# GCDuino3v3.net
KiCad netlist of a schematic drawn in EAGLE
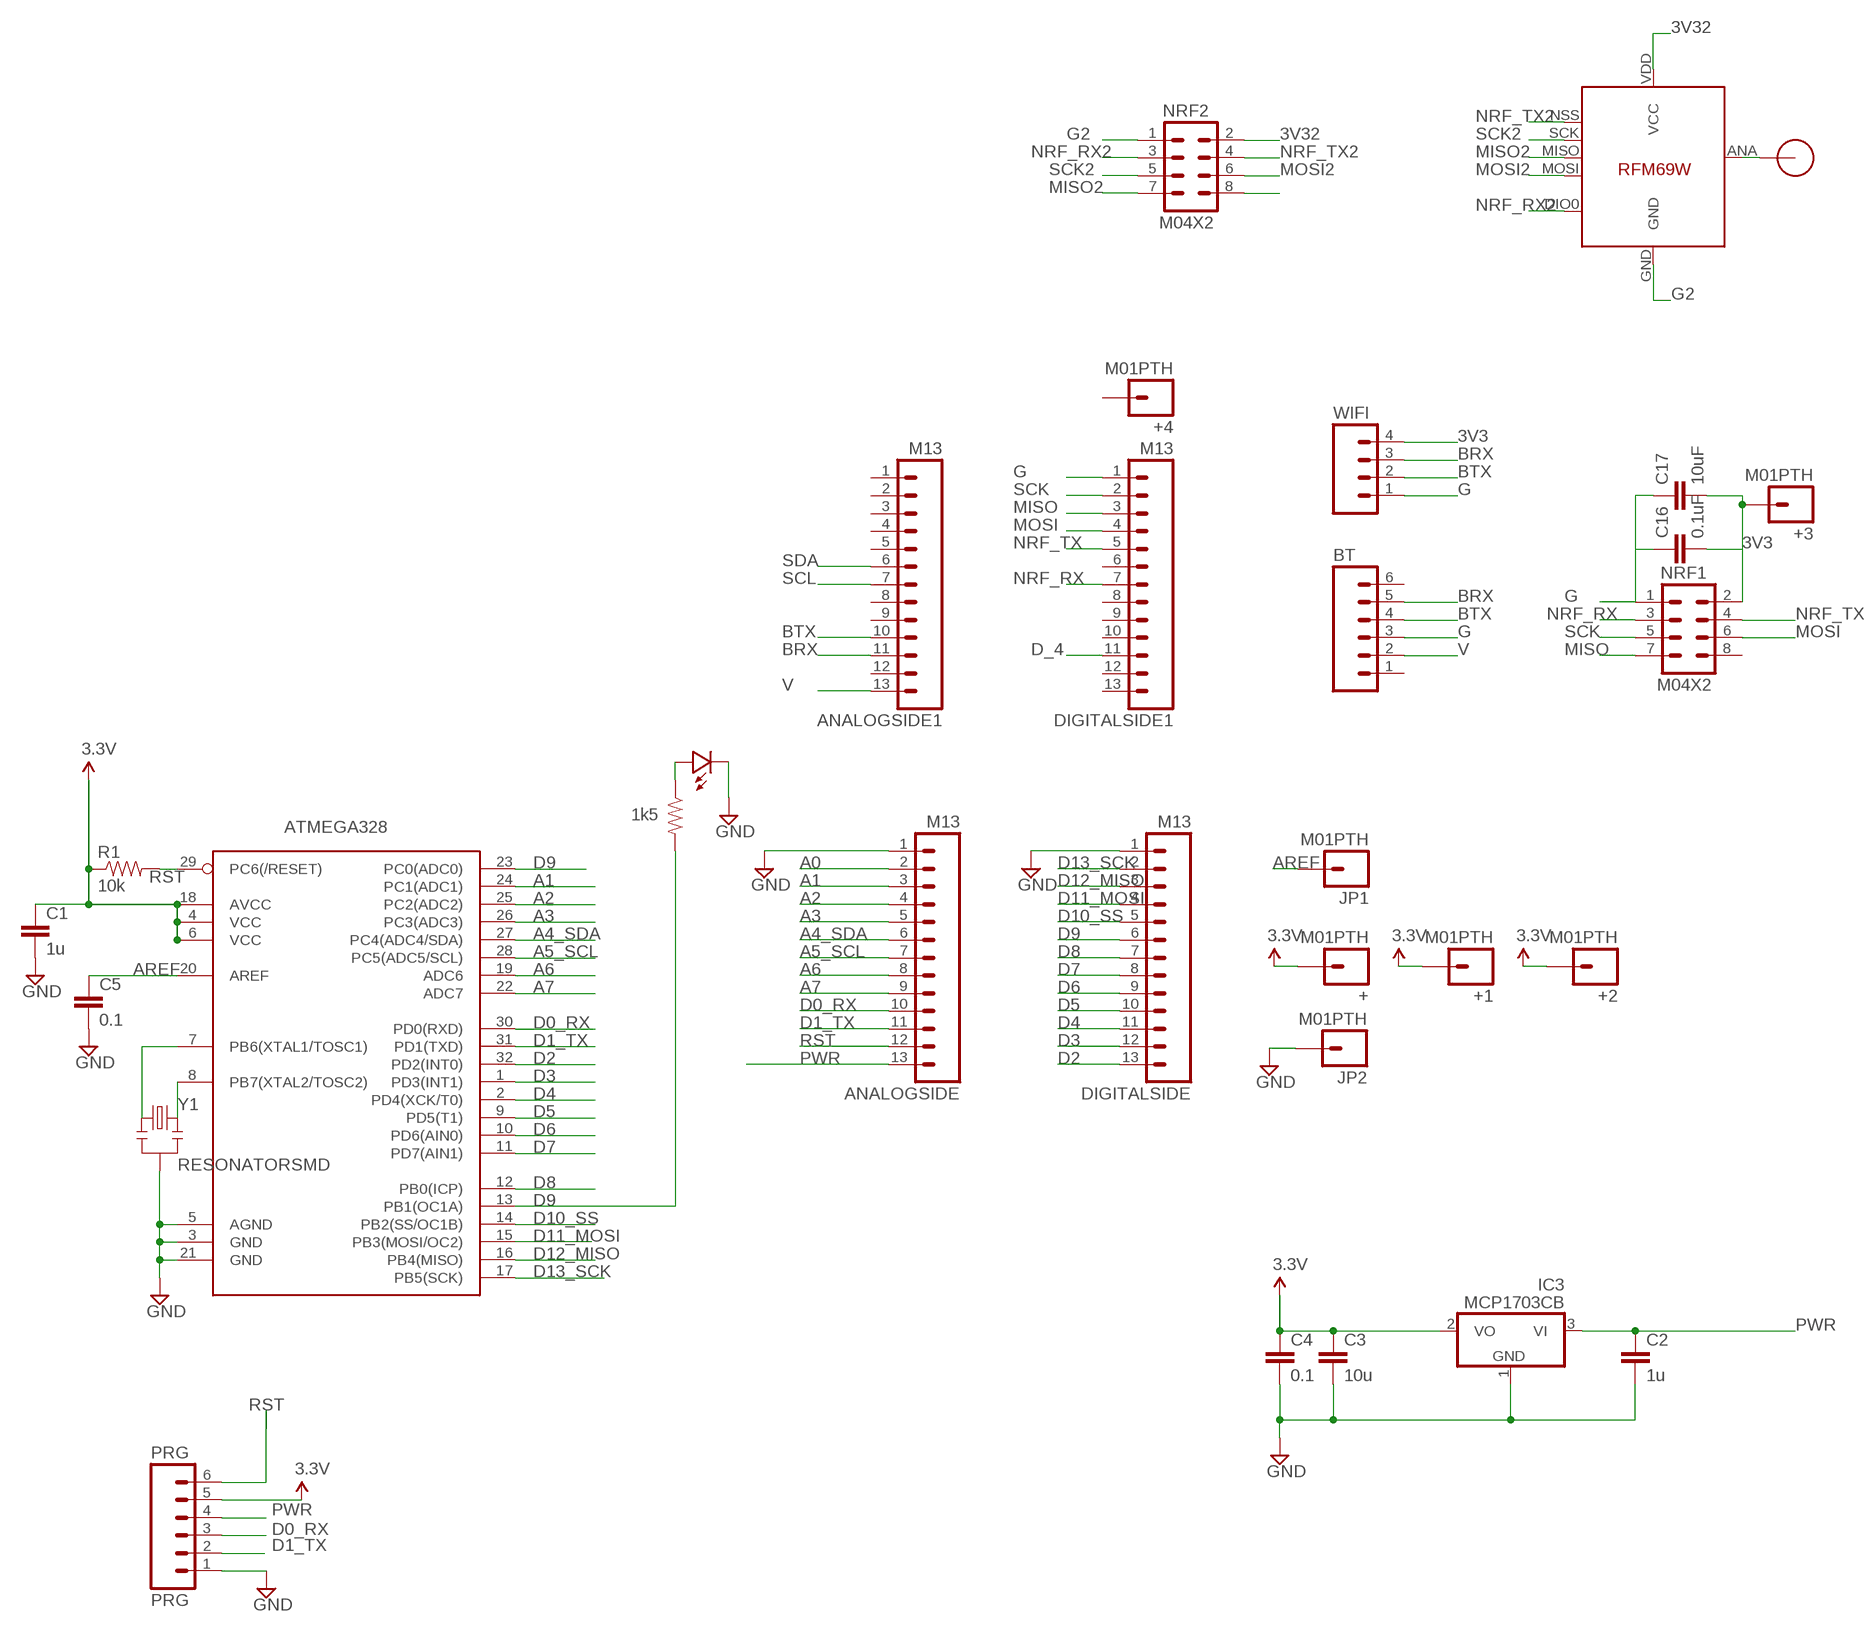
[diagram p0: schematic, sheet 1]

(export (version "E")
  (design (tool "Eeschema 10.0.6"))
  (components
    (comp (ref "+")
      (value "M01PTH")
      (footprint "eagle-import:1X01")
      (libsource (lib "eagle-import") (part "M01PTH"))
    )
    (comp (ref "+1")
      (value "M01PTH")
      (footprint "eagle-import:1X01")
      (libsource (lib "eagle-import") (part "M01PTH"))
    )
    (comp (ref "+2")
      (value "M01PTH")
      (footprint "eagle-import:1X01")
      (libsource (lib "eagle-import") (part "M01PTH"))
    )
    (comp (ref "+3")
      (value "M01PTH")
      (footprint "eagle-import:1X01")
      (libsource (lib "eagle-import") (part "M01PTH"))
    )
    (comp (ref "+4")
      (value "M01PTH")
      (footprint "eagle-import:1X01")
      (libsource (lib "eagle-import") (part "M01PTH"))
    )
    (comp (ref "ANALOGSIDE")
      (value "M13")
      (footprint "eagle-import:1X13")
      (libsource (lib "eagle-import") (part "M13"))
    )
    (comp (ref "ANALOGSIDE1")
      (value "M13")
      (footprint "eagle-import:1X13")
      (libsource (lib "eagle-import") (part "M13"))
    )
    (comp (ref "ATMEGA328")
      (value "ATMega-328")
      (footprint "eagle-import:TQFP32-08")
      (libsource (lib "eagle-import") (part "ATMEGA168/328TQFP32"))
    )
    (comp (ref "BT")
      (value "M06SIP")
      (footprint "eagle-import:1X06")
      (libsource (lib "eagle-import") (part "M06SIP"))
    )
    (comp (ref "C1")
      (value "1u")
      (footprint "eagle-import:0805")
      (libsource (lib "eagle-import") (part "CAP0805"))
    )
    (comp (ref "C2")
      (value "1u")
      (footprint "eagle-import:0805")
      (libsource (lib "eagle-import") (part "CAP0805"))
    )
    (comp (ref "C3")
      (value "10u")
      (footprint "eagle-import:0805-CAP")
      (libsource (lib "eagle-import") (part "CAP0805-CAP"))
    )
    (comp (ref "C4")
      (value "0.1")
      (footprint "eagle-import:0805")
      (libsource (lib "eagle-import") (part "CAP0805"))
    )
    (comp (ref "C5")
      (value "0.1")
      (footprint "eagle-import:0805")
      (libsource (lib "eagle-import") (part "CAP0805"))
    )
    (comp (ref "C16")
      (value "0.1uF")
      (footprint "eagle-import:0805")
      (libsource (lib "eagle-import") (part "SparkFun-Capacitors_CAP0805"))
    )
    (comp (ref "C17")
      (value "10uF")
      (footprint "eagle-import:0805")
      (libsource (lib "eagle-import") (part "SparkFun-Capacitors_CAP0805"))
    )
    (comp (ref "DIGITALSIDE")
      (value "M13")
      (footprint "eagle-import:1X13")
      (libsource (lib "eagle-import") (part "M13"))
    )
    (comp (ref "DIGITALSIDE1")
      (value "M13")
      (footprint "eagle-import:1X13")
      (libsource (lib "eagle-import") (part "M13"))
    )
    (comp (ref "IC3")
      (value "MCP1703CB")
      (footprint "eagle-import:SOT23")
      (libsource (lib "eagle-import") (part "MCP1703CB"))
    )
    (comp (ref "JP1")
      (value "M01PTH")
      (footprint "eagle-import:1X01")
      (libsource (lib "eagle-import") (part "M01PTH"))
    )
    (comp (ref "JP2")
      (value "M01PTH")
      (footprint "eagle-import:1X01")
      (libsource (lib "eagle-import") (part "M01PTH"))
    )
    (comp (ref "NRF1")
      (value "M04X2")
      (footprint "eagle-import:2X4")
      (libsource (lib "eagle-import") (part "M04X2"))
    )
    (comp (ref "NRF2")
      (value "M04X2")
      (footprint "eagle-import:2X4")
      (libsource (lib "eagle-import") (part "M04X2"))
    )
    (comp (ref "PRG")
      (value "PRG")
      (footprint "eagle-import:1X06")
      (libsource (lib "eagle-import") (part "M06SIP"))
    )
    (comp (ref "R1")
      (value "10k")
      (footprint "eagle-import:0805")
      (libsource (lib "eagle-import") (part "RESISTOR0805"))
    )
    (comp (ref "R2")
      (value "1k5")
      (footprint "eagle-import:0805")
      (libsource (lib "eagle-import") (part "RESISTOR0805"))
    )
    (comp (ref "U$2")
      (value "LED0805")
      (footprint "eagle-import:0805-LED")
      (libsource (lib "eagle-import") (part "LED0805"))
    )
    (comp (ref "U$5")
      (value "RFM69")
      (footprint "eagle-import:RFM69W-MINPADS")
      (libsource (lib "eagle-import") (part "RFM69"))
    )
    (comp (ref "U$8")
      (value "RFM12B_ANTENNA")
      (footprint "eagle-import:RFM12B-ANTENNA")
      (libsource (lib "eagle-import") (part "RFM12B_ANTENNA"))
    )
    (comp (ref "WIFI")
      (value "M04PTH")
      (footprint "eagle-import:1X04")
      (libsource (lib "eagle-import") (part "M04PTH"))
    )
    (comp (ref "Y1")
      (value "RESONATORSMD")
      (footprint "eagle-import:RESONATOR-SMD")
      (libsource (lib "eagle-import") (part "RESONATORSMD"))
    )
  )
  (nets
    (net (code "1") (name "/3V3") (class "Default")
      (node (ref "+3") (pin "1") (pinfunction "1_1") (pintype "passive"))
      (node (ref "C16") (pin "2") (pinfunction "2_2") (pintype "passive"))
      (node (ref "C17") (pin "2") (pinfunction "2_2") (pintype "passive"))
      (node (ref "NRF1") (pin "2") (pinfunction "2_2") (pintype "passive"))
      (node (ref "WIFI") (pin "4") (pinfunction "4_4") (pintype "passive"))
    )
    (net (code "2") (name "/3V32") (class "Default")
      (node (ref "NRF2") (pin "2") (pinfunction "2_2") (pintype "passive"))
      (node (ref "U$5") (pin "VDD") (pinfunction "VCC_VDD") (pintype "power_in"))
    )
    (net (code "3") (name "/A0") (class "Default")
      (node (ref "ANALOGSIDE") (pin "2") (pinfunction "2_2") (pintype "passive"))
      (node (ref "ATMEGA328") (pin "23") (pinfunction "PC0(ADC0)_23") (pintype "bidirectional"))
    )
    (net (code "4") (name "/A1") (class "Default")
      (node (ref "ANALOGSIDE") (pin "3") (pinfunction "3_3") (pintype "passive"))
      (node (ref "ATMEGA328") (pin "24") (pinfunction "PC1(ADC1)_24") (pintype "bidirectional"))
    )
    (net (code "5") (name "/A2") (class "Default")
      (node (ref "ANALOGSIDE") (pin "4") (pinfunction "4_4") (pintype "passive"))
      (node (ref "ATMEGA328") (pin "25") (pinfunction "PC2(ADC2)_25") (pintype "bidirectional"))
    )
    (net (code "6") (name "/A3") (class "Default")
      (node (ref "ANALOGSIDE") (pin "5") (pinfunction "5_5") (pintype "passive"))
      (node (ref "ATMEGA328") (pin "26") (pinfunction "PC3(ADC3)_26") (pintype "bidirectional"))
    )
    (net (code "7") (name "/A4_SDA") (class "Default")
      (node (ref "ANALOGSIDE") (pin "6") (pinfunction "6_6") (pintype "passive"))
      (node (ref "ATMEGA328") (pin "27") (pinfunction "PC4(ADC4/SDA)_27") (pintype "bidirectional"))
    )
    (net (code "8") (name "/A5_SCL") (class "Default")
      (node (ref "ANALOGSIDE") (pin "7") (pinfunction "7_7") (pintype "passive"))
      (node (ref "ATMEGA328") (pin "28") (pinfunction "PC5(ADC5/SCL)_28") (pintype "bidirectional"))
    )
    (net (code "9") (name "/A6") (class "Default")
      (node (ref "ANALOGSIDE") (pin "8") (pinfunction "8_8") (pintype "passive"))
      (node (ref "ATMEGA328") (pin "19") (pinfunction "ADC6_19") (pintype "bidirectional"))
    )
    (net (code "10") (name "/A7") (class "Default")
      (node (ref "ANALOGSIDE") (pin "9") (pinfunction "9_9") (pintype "passive"))
      (node (ref "ATMEGA328") (pin "22") (pinfunction "ADC7_22") (pintype "bidirectional"))
    )
    (net (code "11") (name "/AREF") (class "Default")
      (node (ref "ATMEGA328") (pin "20") (pinfunction "AREF_20") (pintype "bidirectional"))
      (node (ref "C5") (pin "1") (pinfunction "1_1") (pintype "passive"))
      (node (ref "JP1") (pin "1") (pinfunction "1_1") (pintype "passive"))
    )
    (net (code "12") (name "/BRX") (class "Default")
      (node (ref "ANALOGSIDE1") (pin "11") (pinfunction "11_11") (pintype "passive"))
      (node (ref "BT") (pin "5") (pinfunction "5_5") (pintype "passive"))
      (node (ref "WIFI") (pin "3") (pinfunction "3_3") (pintype "passive"))
    )
    (net (code "13") (name "/BTX") (class "Default")
      (node (ref "ANALOGSIDE1") (pin "10") (pinfunction "10_10") (pintype "passive"))
      (node (ref "BT") (pin "4") (pinfunction "4_4") (pintype "passive"))
      (node (ref "WIFI") (pin "2") (pinfunction "2_2") (pintype "passive"))
    )
    (net (code "14") (name "/D0_RX") (class "Default")
      (node (ref "ANALOGSIDE") (pin "10") (pinfunction "10_10") (pintype "passive"))
      (node (ref "ATMEGA328") (pin "30") (pinfunction "PD0(RXD)_30") (pintype "bidirectional"))
      (node (ref "PRG") (pin "3") (pinfunction "3_3") (pintype "passive"))
    )
    (net (code "15") (name "/D1_TX") (class "Default")
      (node (ref "ANALOGSIDE") (pin "11") (pinfunction "11_11") (pintype "passive"))
      (node (ref "ATMEGA328") (pin "31") (pinfunction "PD1(TXD)_31") (pintype "bidirectional"))
      (node (ref "PRG") (pin "2") (pinfunction "2_2") (pintype "passive"))
    )
    (net (code "16") (name "/D2") (class "Default")
      (node (ref "ATMEGA328") (pin "32") (pinfunction "PD2(INT0)_32") (pintype "bidirectional"))
      (node (ref "DIGITALSIDE") (pin "13") (pinfunction "13_13") (pintype "passive"))
    )
    (net (code "17") (name "/D3") (class "Default")
      (node (ref "ATMEGA328") (pin "1") (pinfunction "PD3(INT1)_1") (pintype "bidirectional"))
      (node (ref "DIGITALSIDE") (pin "12") (pinfunction "12_12") (pintype "passive"))
    )
    (net (code "18") (name "/D4") (class "Default")
      (node (ref "ATMEGA328") (pin "2") (pinfunction "PD4(XCK/T0)_2") (pintype "bidirectional"))
      (node (ref "DIGITALSIDE") (pin "11") (pinfunction "11_11") (pintype "passive"))
    )
    (net (code "19") (name "/D5") (class "Default")
      (node (ref "ATMEGA328") (pin "9") (pinfunction "PD5(T1)_9") (pintype "bidirectional"))
      (node (ref "DIGITALSIDE") (pin "10") (pinfunction "10_10") (pintype "passive"))
    )
    (net (code "20") (name "/D6") (class "Default")
      (node (ref "ATMEGA328") (pin "10") (pinfunction "PD6(AIN0)_10") (pintype "bidirectional"))
      (node (ref "DIGITALSIDE") (pin "9") (pinfunction "9_9") (pintype "passive"))
    )
    (net (code "21") (name "/D7") (class "Default")
      (node (ref "ATMEGA328") (pin "11") (pinfunction "PD7(AIN1)_11") (pintype "bidirectional"))
      (node (ref "DIGITALSIDE") (pin "8") (pinfunction "8_8") (pintype "passive"))
    )
    (net (code "22") (name "/D8") (class "Default")
      (node (ref "ATMEGA328") (pin "12") (pinfunction "PB0(ICP)_12") (pintype "bidirectional"))
      (node (ref "DIGITALSIDE") (pin "7") (pinfunction "7_7") (pintype "passive"))
    )
    (net (code "23") (name "/D9") (class "Default")
      (node (ref "ATMEGA328") (pin "13") (pinfunction "PB1(OC1A)_13") (pintype "bidirectional"))
      (node (ref "DIGITALSIDE") (pin "6") (pinfunction "6_6") (pintype "passive"))
      (node (ref "R2") (pin "2") (pinfunction "2_2") (pintype "passive"))
    )
    (net (code "24") (name "/D10_SS") (class "Default")
      (node (ref "ATMEGA328") (pin "14") (pinfunction "PB2(SS/OC1B)_14") (pintype "bidirectional"))
      (node (ref "DIGITALSIDE") (pin "5") (pinfunction "5_5") (pintype "passive"))
    )
    (net (code "25") (name "/D11_MOSI") (class "Default")
      (node (ref "ATMEGA328") (pin "15") (pinfunction "PB3(MOSI/OC2)_15") (pintype "bidirectional"))
      (node (ref "DIGITALSIDE") (pin "4") (pinfunction "4_4") (pintype "passive"))
    )
    (net (code "26") (name "/D12_MISO") (class "Default")
      (node (ref "ATMEGA328") (pin "16") (pinfunction "PB4(MISO)_16") (pintype "bidirectional"))
      (node (ref "DIGITALSIDE") (pin "3") (pinfunction "3_3") (pintype "passive"))
    )
    (net (code "27") (name "/D13_SCK") (class "Default")
      (node (ref "ATMEGA328") (pin "17") (pinfunction "PB5(SCK)_17") (pintype "bidirectional"))
      (node (ref "DIGITALSIDE") (pin "2") (pinfunction "2_2") (pintype "passive"))
    )
    (net (code "28") (name "/D_4") (class "Default")
      (node (ref "DIGITALSIDE1") (pin "11") (pinfunction "11_11") (pintype "passive"))
    )
    (net (code "29") (name "/G") (class "Default")
      (node (ref "BT") (pin "3") (pinfunction "3_3") (pintype "passive"))
      (node (ref "C16") (pin "1") (pinfunction "1_1") (pintype "passive"))
      (node (ref "C17") (pin "1") (pinfunction "1_1") (pintype "passive"))
      (node (ref "DIGITALSIDE1") (pin "1") (pinfunction "1_1") (pintype "passive"))
      (node (ref "NRF1") (pin "1") (pinfunction "1_1") (pintype "passive"))
      (node (ref "WIFI") (pin "1") (pinfunction "1_1") (pintype "passive"))
    )
    (net (code "30") (name "/G2") (class "Default")
      (node (ref "NRF2") (pin "1") (pinfunction "1_1") (pintype "passive"))
      (node (ref "U$5") (pin "GND") (pinfunction "GND_GND") (pintype "power_in"))
    )
    (net (code "31") (name "/MISO") (class "Default")
      (node (ref "DIGITALSIDE1") (pin "3") (pinfunction "3_3") (pintype "passive"))
      (node (ref "NRF1") (pin "7") (pinfunction "7_7") (pintype "passive"))
    )
    (net (code "32") (name "/MISO2") (class "Default")
      (node (ref "NRF2") (pin "7") (pinfunction "7_7") (pintype "passive"))
      (node (ref "U$5") (pin "MISO") (pinfunction "MISO_MISO") (pintype "input"))
    )
    (net (code "33") (name "/MOSI") (class "Default")
      (node (ref "DIGITALSIDE1") (pin "4") (pinfunction "4_4") (pintype "passive"))
      (node (ref "NRF1") (pin "6") (pinfunction "6_6") (pintype "passive"))
    )
    (net (code "34") (name "/MOSI2") (class "Default")
      (node (ref "NRF2") (pin "6") (pinfunction "6_6") (pintype "passive"))
      (node (ref "U$5") (pin "MOSI") (pinfunction "MOSI_MOSI") (pintype "output"))
    )
    (net (code "35") (name "/NRF_RX") (class "Default")
      (node (ref "DIGITALSIDE1") (pin "7") (pinfunction "7_7") (pintype "passive"))
      (node (ref "NRF1") (pin "3") (pinfunction "3_3") (pintype "passive"))
    )
    (net (code "36") (name "/NRF_RX2") (class "Default")
      (node (ref "NRF2") (pin "3") (pinfunction "3_3") (pintype "passive"))
      (node (ref "U$5") (pin "DIO0") (pinfunction "DIO0_DIO0") (pintype "open_collector"))
    )
    (net (code "37") (name "/NRF_TX") (class "Default")
      (node (ref "DIGITALSIDE1") (pin "5") (pinfunction "5_5") (pintype "passive"))
      (node (ref "NRF1") (pin "4") (pinfunction "4_4") (pintype "passive"))
    )
    (net (code "38") (name "/NRF_TX2") (class "Default")
      (node (ref "NRF2") (pin "4") (pinfunction "4_4") (pintype "passive"))
      (node (ref "U$5") (pin "NSS") (pinfunction "SEL_NSS") (pintype "input"))
    )
    (net (code "39") (name "/PWR") (class "Default")
      (node (ref "ANALOGSIDE") (pin "13") (pinfunction "13_13") (pintype "passive"))
      (node (ref "C2") (pin "1") (pinfunction "1_1") (pintype "passive"))
      (node (ref "IC3") (pin "3") (pinfunction "VI_3") (pintype "input"))
      (node (ref "PRG") (pin "4") (pinfunction "4_4") (pintype "passive"))
    )
    (net (code "40") (name "/RST") (class "Default")
      (node (ref "ANALOGSIDE") (pin "12") (pinfunction "12_12") (pintype "passive"))
      (node (ref "ATMEGA328") (pin "29") (pinfunction "PC6(/RESET)_29") (pintype "bidirectional"))
      (node (ref "PRG") (pin "6") (pinfunction "6_6") (pintype "passive"))
      (node (ref "R1") (pin "2") (pinfunction "2_2") (pintype "passive"))
    )
    (net (code "41") (name "/SCK") (class "Default")
      (node (ref "DIGITALSIDE1") (pin "2") (pinfunction "2_2") (pintype "passive"))
      (node (ref "NRF1") (pin "5") (pinfunction "5_5") (pintype "passive"))
    )
    (net (code "42") (name "/SCK2") (class "Default")
      (node (ref "NRF2") (pin "5") (pinfunction "5_5") (pintype "passive"))
      (node (ref "U$5") (pin "SCK") (pinfunction "SCK_SCK") (pintype "input"))
    )
    (net (code "43") (name "/SCL") (class "Default")
      (node (ref "ANALOGSIDE1") (pin "7") (pinfunction "7_7") (pintype "passive"))
    )
    (net (code "44") (name "/SDA") (class "Default")
      (node (ref "ANALOGSIDE1") (pin "6") (pinfunction "6_6") (pintype "passive"))
    )
    (net (code "45") (name "/V") (class "Default")
      (node (ref "ANALOGSIDE1") (pin "13") (pinfunction "13_13") (pintype "passive"))
      (node (ref "BT") (pin "2") (pinfunction "2_2") (pintype "passive"))
    )
    (net (code "46") (name "3.3V") (class "Default")
      (node (ref "+") (pin "1") (pinfunction "1_1") (pintype "passive"))
      (node (ref "+1") (pin "1") (pinfunction "1_1") (pintype "passive"))
      (node (ref "+2") (pin "1") (pinfunction "1_1") (pintype "passive"))
      (node (ref "ATMEGA328") (pin "18") (pinfunction "AVCC_18") (pintype "bidirectional"))
      (node (ref "ATMEGA328") (pin "4") (pinfunction "VCC_4") (pintype "bidirectional"))
      (node (ref "ATMEGA328") (pin "6") (pinfunction "VCC_6") (pintype "bidirectional"))
      (node (ref "C1") (pin "1") (pinfunction "1_1") (pintype "passive"))
      (node (ref "C3") (pin "1") (pinfunction "1_1") (pintype "passive"))
      (node (ref "C4") (pin "1") (pinfunction "1_1") (pintype "passive"))
      (node (ref "IC3") (pin "2") (pinfunction "VO_2") (pintype "passive"))
      (node (ref "PRG") (pin "5") (pinfunction "5_5") (pintype "passive"))
      (node (ref "R1") (pin "1") (pinfunction "1_1") (pintype "passive"))
    )
    (net (code "47") (name "GND") (class "Default")
      (node (ref "ANALOGSIDE") (pin "1") (pinfunction "1_1") (pintype "passive"))
      (node (ref "ATMEGA328") (pin "21") (pinfunction "GND_21") (pintype "bidirectional"))
      (node (ref "ATMEGA328") (pin "3") (pinfunction "GND_3") (pintype "bidirectional"))
      (node (ref "ATMEGA328") (pin "5") (pinfunction "AGND_5") (pintype "bidirectional"))
      (node (ref "C1") (pin "2") (pinfunction "2_2") (pintype "passive"))
      (node (ref "C2") (pin "2") (pinfunction "2_2") (pintype "passive"))
      (node (ref "C3") (pin "2") (pinfunction "2_2") (pintype "passive"))
      (node (ref "C4") (pin "2") (pinfunction "2_2") (pintype "passive"))
      (node (ref "C5") (pin "2") (pinfunction "2_2") (pintype "passive"))
      (node (ref "DIGITALSIDE") (pin "1") (pinfunction "1_1") (pintype "passive"))
      (node (ref "IC3") (pin "1") (pinfunction "GND_1") (pintype "passive"))
      (node (ref "JP2") (pin "1") (pinfunction "1_1") (pintype "passive"))
      (node (ref "PRG") (pin "1") (pinfunction "1_1") (pintype "passive"))
      (node (ref "U$2") (pin "MINUS") (pinfunction "MINUS_MINUS") (pintype "passive"))
      (node (ref "Y1") (pin "2") (pinfunction "2_2") (pintype "passive"))
    )
    (net (code "48") (name "Net-(ATMEGA328-PB6(XTAL1{slash}TOSC1))") (class "Default")
      (node (ref "ATMEGA328") (pin "7") (pinfunction "PB6(XTAL1/TOSC1)_7") (pintype "bidirectional"))
      (node (ref "Y1") (pin "1") (pinfunction "1_1") (pintype "passive"))
    )
    (net (code "49") (name "Net-(ATMEGA328-PB7(XTAL2{slash}TOSC2))") (class "Default")
      (node (ref "ATMEGA328") (pin "8") (pinfunction "PB7(XTAL2/TOSC2)_8") (pintype "bidirectional"))
      (node (ref "Y1") (pin "3") (pinfunction "3_3") (pintype "passive"))
    )
    (net (code "50") (name "Net-(R2-Pad1)") (class "Default")
      (node (ref "R2") (pin "1") (pinfunction "1_1") (pintype "passive"))
      (node (ref "U$2") (pin "PLUS") (pinfunction "PLUS_PLUS") (pintype "passive"))
    )
    (net (code "51") (name "Net-(U$5-ANT)") (class "Default")
      (node (ref "U$5") (pin "ANA") (pinfunction "ANT_ANA") (pintype "passive"))
      (node (ref "U$8") (pin "P$1") (pinfunction "1_P$1") (pintype "bidirectional"))
    )
    (net (code "52") (name "unconnected-(+4-Pad1)") (class "Default")
      (node (ref "+4") (pin "1") (pinfunction "1_1") (pintype "passive"))
    )
    (net (code "53") (name "unconnected-(ANALOGSIDE1-Pad1)") (class "Default")
      (node (ref "ANALOGSIDE1") (pin "1") (pinfunction "1_1") (pintype "passive"))
    )
    (net (code "54") (name "unconnected-(ANALOGSIDE1-Pad2)") (class "Default")
      (node (ref "ANALOGSIDE1") (pin "2") (pinfunction "2_2") (pintype "passive"))
    )
    (net (code "55") (name "unconnected-(ANALOGSIDE1-Pad3)") (class "Default")
      (node (ref "ANALOGSIDE1") (pin "3") (pinfunction "3_3") (pintype "passive"))
    )
    (net (code "56") (name "unconnected-(ANALOGSIDE1-Pad4)") (class "Default")
      (node (ref "ANALOGSIDE1") (pin "4") (pinfunction "4_4") (pintype "passive"))
    )
    (net (code "57") (name "unconnected-(ANALOGSIDE1-Pad5)") (class "Default")
      (node (ref "ANALOGSIDE1") (pin "5") (pinfunction "5_5") (pintype "passive"))
    )
    (net (code "58") (name "unconnected-(ANALOGSIDE1-Pad8)") (class "Default")
      (node (ref "ANALOGSIDE1") (pin "8") (pinfunction "8_8") (pintype "passive"))
    )
    (net (code "59") (name "unconnected-(ANALOGSIDE1-Pad9)") (class "Default")
      (node (ref "ANALOGSIDE1") (pin "9") (pinfunction "9_9") (pintype "passive"))
    )
    (net (code "60") (name "unconnected-(ANALOGSIDE1-Pad12)") (class "Default")
      (node (ref "ANALOGSIDE1") (pin "12") (pinfunction "12_12") (pintype "passive"))
    )
    (net (code "61") (name "unconnected-(BT-Pad1)") (class "Default")
      (node (ref "BT") (pin "1") (pinfunction "1_1") (pintype "passive"))
    )
    (net (code "62") (name "unconnected-(BT-Pad6)") (class "Default")
      (node (ref "BT") (pin "6") (pinfunction "6_6") (pintype "passive"))
    )
    (net (code "63") (name "unconnected-(DIGITALSIDE1-Pad6)") (class "Default")
      (node (ref "DIGITALSIDE1") (pin "6") (pinfunction "6_6") (pintype "passive"))
    )
    (net (code "64") (name "unconnected-(DIGITALSIDE1-Pad8)") (class "Default")
      (node (ref "DIGITALSIDE1") (pin "8") (pinfunction "8_8") (pintype "passive"))
    )
    (net (code "65") (name "unconnected-(DIGITALSIDE1-Pad9)") (class "Default")
      (node (ref "DIGITALSIDE1") (pin "9") (pinfunction "9_9") (pintype "passive"))
    )
    (net (code "66") (name "unconnected-(DIGITALSIDE1-Pad10)") (class "Default")
      (node (ref "DIGITALSIDE1") (pin "10") (pinfunction "10_10") (pintype "passive"))
    )
    (net (code "67") (name "unconnected-(DIGITALSIDE1-Pad12)") (class "Default")
      (node (ref "DIGITALSIDE1") (pin "12") (pinfunction "12_12") (pintype "passive"))
    )
    (net (code "68") (name "unconnected-(DIGITALSIDE1-Pad13)") (class "Default")
      (node (ref "DIGITALSIDE1") (pin "13") (pinfunction "13_13") (pintype "passive"))
    )
    (net (code "69") (name "unconnected-(NRF1-Pad8)") (class "Default")
      (node (ref "NRF1") (pin "8") (pinfunction "8_8") (pintype "passive"))
    )
    (net (code "70") (name "unconnected-(NRF2-Pad8)") (class "Default")
      (node (ref "NRF2") (pin "8") (pinfunction "8_8") (pintype "passive"))
    )
  )
)
